# CoreDuino.net
KiCad netlist of a schematic drawn in EAGLE
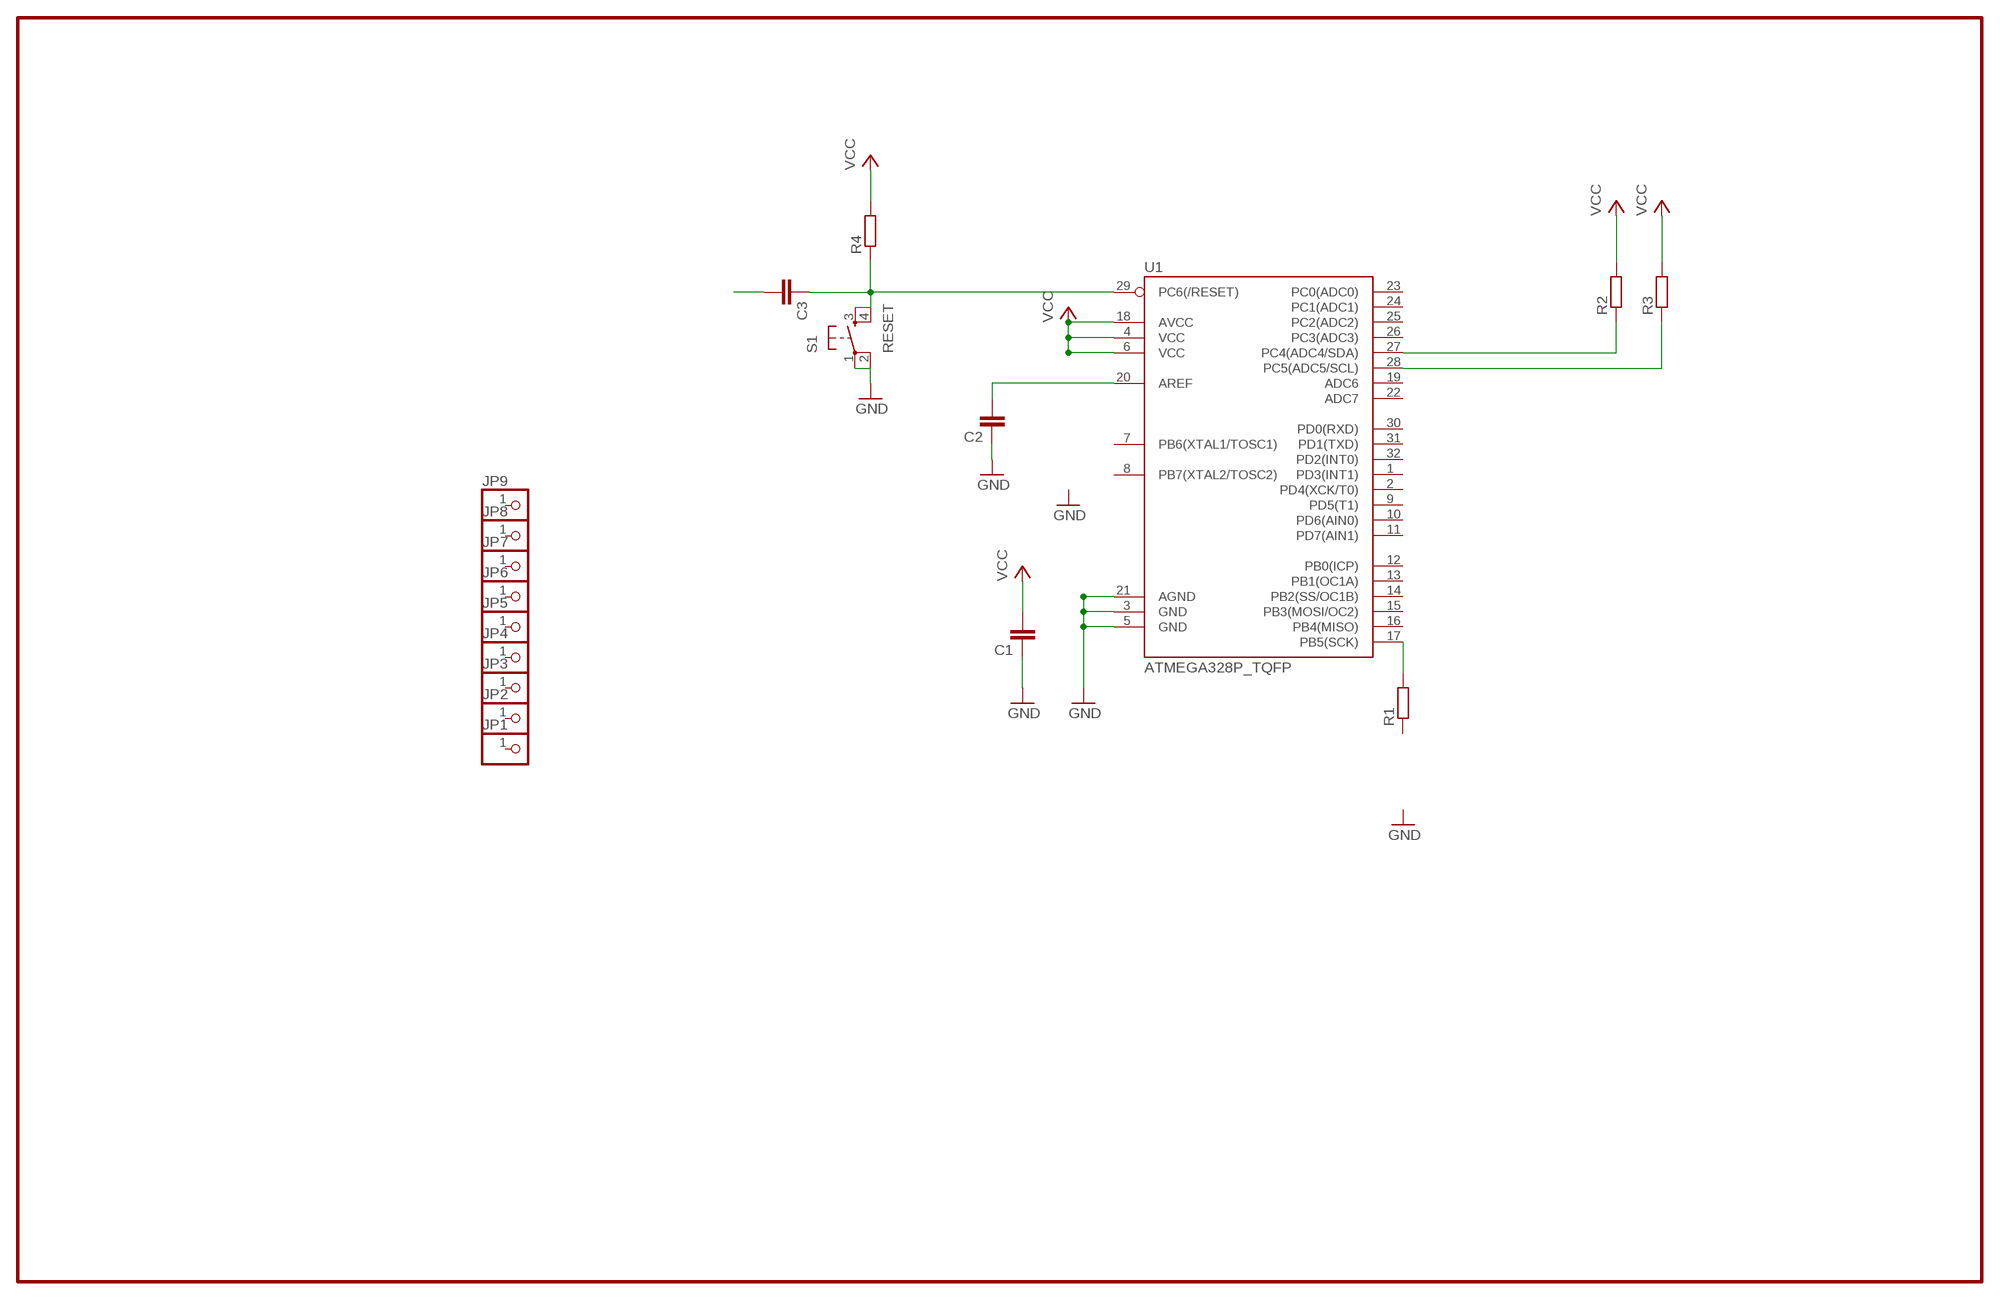
[diagram p0: schematic, sheet 1]

(export (version "E")
  (design (tool "Eeschema 10.0.6"))
  (components
    (comp (ref "C1")
      (value "C-EUC0805")
      (footprint "eagle-import:C0805")
      (libsource (lib "eagle-import") (part "C-EUC0805"))
    )
    (comp (ref "C2")
      (value "C-EUC0805")
      (footprint "eagle-import:C0805")
      (libsource (lib "eagle-import") (part "C-EUC0805"))
    )
    (comp (ref "C3")
      (value "C-EUC0805")
      (footprint "eagle-import:C0805")
      (libsource (lib "eagle-import") (part "C-EUC0805"))
    )
    (comp (ref "JP1")
      (value "PINHD-1X1CB")
      (footprint "eagle-import:1X01-CLEANBIG")
      (libsource (lib "eagle-import") (part "PINHD-1X1CB"))
    )
    (comp (ref "JP2")
      (value "PINHD-1X1CB")
      (footprint "eagle-import:1X01-CLEANBIG")
      (libsource (lib "eagle-import") (part "PINHD-1X1CB"))
    )
    (comp (ref "JP3")
      (value "PINHD-1X1CB")
      (footprint "eagle-import:1X01-CLEANBIG")
      (libsource (lib "eagle-import") (part "PINHD-1X1CB"))
    )
    (comp (ref "JP4")
      (value "PINHD-1X1CB")
      (footprint "eagle-import:1X01-CLEANBIG")
      (libsource (lib "eagle-import") (part "PINHD-1X1CB"))
    )
    (comp (ref "JP5")
      (value "PINHD-1X1CB")
      (footprint "eagle-import:1X01-CLEANBIG")
      (libsource (lib "eagle-import") (part "PINHD-1X1CB"))
    )
    (comp (ref "JP6")
      (value "PINHD-1X1CB")
      (footprint "eagle-import:1X01-CLEANBIG")
      (libsource (lib "eagle-import") (part "PINHD-1X1CB"))
    )
    (comp (ref "JP7")
      (value "PINHD-1X1CB")
      (footprint "eagle-import:1X01-CLEANBIG")
      (libsource (lib "eagle-import") (part "PINHD-1X1CB"))
    )
    (comp (ref "JP8")
      (value "PINHD-1X1CB")
      (footprint "eagle-import:1X01-CLEANBIG")
      (libsource (lib "eagle-import") (part "PINHD-1X1CB"))
    )
    (comp (ref "JP9")
      (value "PINHD-1X1CB")
      (footprint "eagle-import:1X01-CLEANBIG")
      (libsource (lib "eagle-import") (part "PINHD-1X1CB"))
    )
    (comp (ref "R1")
      (value "R-EU_R0805")
      (footprint "eagle-import:R0805")
      (libsource (lib "eagle-import") (part "R-EU_R0805"))
    )
    (comp (ref "R2")
      (value "R-EU_R0805")
      (footprint "eagle-import:R0805")
      (libsource (lib "eagle-import") (part "R-EU_R0805"))
    )
    (comp (ref "R3")
      (value "R-EU_R0805")
      (footprint "eagle-import:R0805")
      (libsource (lib "eagle-import") (part "R-EU_R0805"))
    )
    (comp (ref "R4")
      (value "R-EU_R0805")
      (footprint "eagle-import:R0805")
      (libsource (lib "eagle-import") (part "R-EU_R0805"))
    )
    (comp (ref "S1")
      (value "RESET")
      (footprint "eagle-import:TACTILE-SWITCH-SMD")
      (libsource (lib "eagle-import") (part "TAC_SWITCHSMD"))
    )
    (comp (ref "U1")
      (value "ATMEGA328P_TQFP")
      (footprint "eagle-import:TQFP32-08")
      (libsource (lib "eagle-import") (part "ATMEGA328P_TQFP"))
    )
  )
  (nets
    (net (code "1") (name "GND") (class "Default")
      (node (ref "C1") (pin "1") (pinfunction "1_1") (pintype "passive"))
      (node (ref "C2") (pin "1") (pinfunction "1_1") (pintype "passive"))
      (node (ref "S1") (pin "1") (pinfunction "1_1") (pintype "passive"))
      (node (ref "S1") (pin "2") (pinfunction "2_2") (pintype "passive"))
      (node (ref "U1") (pin "21") (pinfunction "AGND_21") (pintype "bidirectional"))
      (node (ref "U1") (pin "3") (pinfunction "GND_3") (pintype "bidirectional"))
      (node (ref "U1") (pin "5") (pinfunction "GND_5") (pintype "bidirectional"))
    )
    (net (code "2") (name "Net-(U1-AREF)") (class "Default")
      (node (ref "C2") (pin "2") (pinfunction "2_2") (pintype "passive"))
      (node (ref "U1") (pin "20") (pinfunction "AREF_20") (pintype "bidirectional"))
    )
    (net (code "3") (name "Net-(U1-PB5(SCK))") (class "Default")
      (node (ref "R1") (pin "2") (pinfunction "2_2") (pintype "passive"))
      (node (ref "U1") (pin "17") (pinfunction "PB5(SCK)_17") (pintype "bidirectional"))
    )
    (net (code "4") (name "Net-(U1-PC4(ADC4{slash}SDA))") (class "Default")
      (node (ref "R2") (pin "1") (pinfunction "1_1") (pintype "passive"))
      (node (ref "U1") (pin "27") (pinfunction "PC4(ADC4/SDA)_27") (pintype "bidirectional"))
    )
    (net (code "5") (name "Net-(U1-PC5(ADC5{slash}SCL))") (class "Default")
      (node (ref "R3") (pin "1") (pinfunction "1_1") (pintype "passive"))
      (node (ref "U1") (pin "28") (pinfunction "PC5(ADC5/SCL)_28") (pintype "bidirectional"))
    )
    (net (code "6") (name "Net-(U1-PC6({slash}RESET))") (class "Default")
      (node (ref "C3") (pin "1") (pinfunction "1_1") (pintype "passive"))
      (node (ref "R4") (pin "1") (pinfunction "1_1") (pintype "passive"))
      (node (ref "S1") (pin "3") (pinfunction "3_3") (pintype "passive"))
      (node (ref "S1") (pin "4") (pinfunction "4_4") (pintype "passive"))
      (node (ref "U1") (pin "29") (pinfunction "PC6(/RESET)_29") (pintype "bidirectional"))
    )
    (net (code "7") (name "VCC") (class "Default")
      (node (ref "C1") (pin "2") (pinfunction "2_2") (pintype "passive"))
      (node (ref "R2") (pin "2") (pinfunction "2_2") (pintype "passive"))
      (node (ref "R3") (pin "2") (pinfunction "2_2") (pintype "passive"))
      (node (ref "R4") (pin "2") (pinfunction "2_2") (pintype "passive"))
      (node (ref "U1") (pin "18") (pinfunction "AVCC_18") (pintype "bidirectional"))
      (node (ref "U1") (pin "4") (pinfunction "VCC_4") (pintype "bidirectional"))
      (node (ref "U1") (pin "6") (pinfunction "VCC_6") (pintype "bidirectional"))
    )
    (net (code "8") (name "unconnected-(C3-Pad2)") (class "Default")
      (node (ref "C3") (pin "2") (pinfunction "2_2") (pintype "passive"))
    )
    (net (code "9") (name "unconnected-(JP1-Pad1)") (class "Default")
      (node (ref "JP1") (pin "1") (pinfunction "1_1") (pintype "passive"))
    )
    (net (code "10") (name "unconnected-(JP2-Pad1)") (class "Default")
      (node (ref "JP2") (pin "1") (pinfunction "1_1") (pintype "passive"))
    )
    (net (code "11") (name "unconnected-(JP3-Pad1)") (class "Default")
      (node (ref "JP3") (pin "1") (pinfunction "1_1") (pintype "passive"))
    )
    (net (code "12") (name "unconnected-(JP4-Pad1)") (class "Default")
      (node (ref "JP4") (pin "1") (pinfunction "1_1") (pintype "passive"))
    )
    (net (code "13") (name "unconnected-(JP5-Pad1)") (class "Default")
      (node (ref "JP5") (pin "1") (pinfunction "1_1") (pintype "passive"))
    )
    (net (code "14") (name "unconnected-(JP6-Pad1)") (class "Default")
      (node (ref "JP6") (pin "1") (pinfunction "1_1") (pintype "passive"))
    )
    (net (code "15") (name "unconnected-(JP7-Pad1)") (class "Default")
      (node (ref "JP7") (pin "1") (pinfunction "1_1") (pintype "passive"))
    )
    (net (code "16") (name "unconnected-(JP8-Pad1)") (class "Default")
      (node (ref "JP8") (pin "1") (pinfunction "1_1") (pintype "passive"))
    )
    (net (code "17") (name "unconnected-(JP9-Pad1)") (class "Default")
      (node (ref "JP9") (pin "1") (pinfunction "1_1") (pintype "passive"))
    )
    (net (code "18") (name "unconnected-(R1-Pad1)") (class "Default")
      (node (ref "R1") (pin "1") (pinfunction "1_1") (pintype "passive"))
    )
    (net (code "19") (name "unconnected-(U1-ADC6-Pad19)") (class "Default")
      (node (ref "U1") (pin "19") (pinfunction "ADC6_19") (pintype "bidirectional"))
    )
    (net (code "20") (name "unconnected-(U1-ADC7-Pad22)") (class "Default")
      (node (ref "U1") (pin "22") (pinfunction "ADC7_22") (pintype "bidirectional"))
    )
    (net (code "21") (name "unconnected-(U1-PB0(ICP)-Pad12)") (class "Default")
      (node (ref "U1") (pin "12") (pinfunction "PB0(ICP)_12") (pintype "bidirectional"))
    )
    (net (code "22") (name "unconnected-(U1-PB1(OC1A)-Pad13)") (class "Default")
      (node (ref "U1") (pin "13") (pinfunction "PB1(OC1A)_13") (pintype "bidirectional"))
    )
    (net (code "23") (name "unconnected-(U1-PB2(SS{slash}OC1B)-Pad14)") (class "Default")
      (node (ref "U1") (pin "14") (pinfunction "PB2(SS/OC1B)_14") (pintype "bidirectional"))
    )
    (net (code "24") (name "unconnected-(U1-PB3(MOSI{slash}OC2)-Pad15)") (class "Default")
      (node (ref "U1") (pin "15") (pinfunction "PB3(MOSI/OC2)_15") (pintype "bidirectional"))
    )
    (net (code "25") (name "unconnected-(U1-PB4(MISO)-Pad16)") (class "Default")
      (node (ref "U1") (pin "16") (pinfunction "PB4(MISO)_16") (pintype "bidirectional"))
    )
    (net (code "26") (name "unconnected-(U1-PB6(XTAL1{slash}TOSC1)-Pad7)") (class "Default")
      (node (ref "U1") (pin "7") (pinfunction "PB6(XTAL1/TOSC1)_7") (pintype "bidirectional"))
    )
    (net (code "27") (name "unconnected-(U1-PB7(XTAL2{slash}TOSC2)-Pad8)") (class "Default")
      (node (ref "U1") (pin "8") (pinfunction "PB7(XTAL2/TOSC2)_8") (pintype "bidirectional"))
    )
    (net (code "28") (name "unconnected-(U1-PC0(ADC0)-Pad23)") (class "Default")
      (node (ref "U1") (pin "23") (pinfunction "PC0(ADC0)_23") (pintype "bidirectional"))
    )
    (net (code "29") (name "unconnected-(U1-PC1(ADC1)-Pad24)") (class "Default")
      (node (ref "U1") (pin "24") (pinfunction "PC1(ADC1)_24") (pintype "bidirectional"))
    )
    (net (code "30") (name "unconnected-(U1-PC2(ADC2)-Pad25)") (class "Default")
      (node (ref "U1") (pin "25") (pinfunction "PC2(ADC2)_25") (pintype "bidirectional"))
    )
    (net (code "31") (name "unconnected-(U1-PC3(ADC3)-Pad26)") (class "Default")
      (node (ref "U1") (pin "26") (pinfunction "PC3(ADC3)_26") (pintype "bidirectional"))
    )
    (net (code "32") (name "unconnected-(U1-PD0(RXD)-Pad30)") (class "Default")
      (node (ref "U1") (pin "30") (pinfunction "PD0(RXD)_30") (pintype "bidirectional"))
    )
    (net (code "33") (name "unconnected-(U1-PD1(TXD)-Pad31)") (class "Default")
      (node (ref "U1") (pin "31") (pinfunction "PD1(TXD)_31") (pintype "bidirectional"))
    )
    (net (code "34") (name "unconnected-(U1-PD2(INT0)-Pad32)") (class "Default")
      (node (ref "U1") (pin "32") (pinfunction "PD2(INT0)_32") (pintype "bidirectional"))
    )
    (net (code "35") (name "unconnected-(U1-PD3(INT1)-Pad1)") (class "Default")
      (node (ref "U1") (pin "1") (pinfunction "PD3(INT1)_1") (pintype "bidirectional"))
    )
    (net (code "36") (name "unconnected-(U1-PD4(XCK{slash}T0)-Pad2)") (class "Default")
      (node (ref "U1") (pin "2") (pinfunction "PD4(XCK/T0)_2") (pintype "bidirectional"))
    )
    (net (code "37") (name "unconnected-(U1-PD5(T1)-Pad9)") (class "Default")
      (node (ref "U1") (pin "9") (pinfunction "PD5(T1)_9") (pintype "bidirectional"))
    )
    (net (code "38") (name "unconnected-(U1-PD6(AIN0)-Pad10)") (class "Default")
      (node (ref "U1") (pin "10") (pinfunction "PD6(AIN0)_10") (pintype "bidirectional"))
    )
    (net (code "39") (name "unconnected-(U1-PD7(AIN1)-Pad11)") (class "Default")
      (node (ref "U1") (pin "11") (pinfunction "PD7(AIN1)_11") (pintype "bidirectional"))
    )
  )
)
